# anna-b112-to-dip.net
KiCad netlist of a schematic drawn in EAGLE
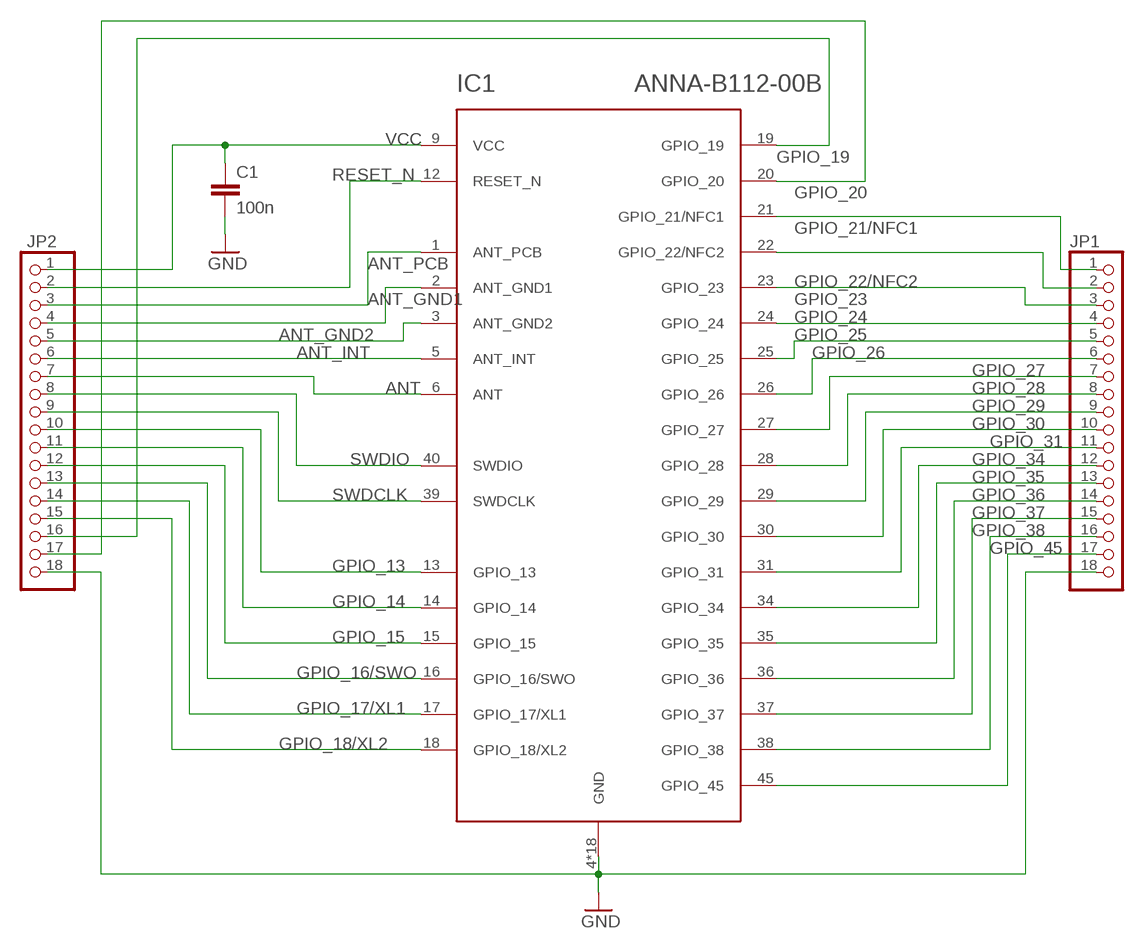
[diagram p0: schematic, sheet 1]

(export (version "E")
  (design (tool "Eeschema 10.0.6"))
  (components
    (comp (ref "C1")
      (value "100n")
      (footprint "eagle-import:C0805")
      (libsource (lib "eagle-import") (part "C-EUC0805"))
    )
    (comp (ref "IC1")
      (value "ANNA-B112-00B")
      (footprint "eagle-import:ANNA-B112")
      (libsource (lib "eagle-import") (part "ANNA-B112-00B"))
    )
    (comp (ref "JP1")
      (value "PINHD-1X18")
      (footprint "eagle-import:1X18")
      (libsource (lib "eagle-import") (part "PINHD-1X18"))
    )
    (comp (ref "JP2")
      (value "PINHD-1X18")
      (footprint "eagle-import:1X18")
      (libsource (lib "eagle-import") (part "PINHD-1X18"))
    )
  )
  (nets
    (net (code "1") (name "/ANT") (class "Default")
      (node (ref "IC1") (pin "6") (pinfunction "ANT_6") (pintype "bidirectional"))
      (node (ref "JP2") (pin "7") (pinfunction "7_7") (pintype "passive"))
    )
    (net (code "2") (name "/ANT_GND1") (class "Default")
      (node (ref "IC1") (pin "2") (pinfunction "ANT_GND1_2") (pintype "bidirectional"))
      (node (ref "JP2") (pin "4") (pinfunction "4_4") (pintype "passive"))
    )
    (net (code "3") (name "/ANT_GND2") (class "Default")
      (node (ref "IC1") (pin "3") (pinfunction "ANT_GND2_3") (pintype "bidirectional"))
      (node (ref "JP2") (pin "5") (pinfunction "5_5") (pintype "passive"))
    )
    (net (code "4") (name "/ANT_INT") (class "Default")
      (node (ref "IC1") (pin "5") (pinfunction "ANT_INT_5") (pintype "bidirectional"))
      (node (ref "JP2") (pin "6") (pinfunction "6_6") (pintype "passive"))
    )
    (net (code "5") (name "/ANT_PCB") (class "Default")
      (node (ref "IC1") (pin "1") (pinfunction "ANT_PCB_1") (pintype "bidirectional"))
      (node (ref "JP2") (pin "3") (pinfunction "3_3") (pintype "passive"))
    )
    (net (code "6") (name "/GPIO_13") (class "Default")
      (node (ref "IC1") (pin "13") (pinfunction "GPIO_13_13") (pintype "bidirectional"))
      (node (ref "JP2") (pin "10") (pinfunction "10_10") (pintype "passive"))
    )
    (net (code "7") (name "/GPIO_14") (class "Default")
      (node (ref "IC1") (pin "14") (pinfunction "GPIO_14_14") (pintype "bidirectional"))
      (node (ref "JP2") (pin "11") (pinfunction "11_11") (pintype "passive"))
    )
    (net (code "8") (name "/GPIO_15") (class "Default")
      (node (ref "IC1") (pin "15") (pinfunction "GPIO_15_15") (pintype "bidirectional"))
      (node (ref "JP2") (pin "12") (pinfunction "12_12") (pintype "passive"))
    )
    (net (code "9") (name "/GPIO_16{slash}SWO") (class "Default")
      (node (ref "IC1") (pin "16") (pinfunction "GPIO_16/SWO_16") (pintype "bidirectional"))
      (node (ref "JP2") (pin "13") (pinfunction "13_13") (pintype "passive"))
    )
    (net (code "10") (name "/GPIO_17{slash}XL1") (class "Default")
      (node (ref "IC1") (pin "17") (pinfunction "GPIO_17/XL1_17") (pintype "bidirectional"))
      (node (ref "JP2") (pin "14") (pinfunction "14_14") (pintype "passive"))
    )
    (net (code "11") (name "/GPIO_18{slash}XL2") (class "Default")
      (node (ref "IC1") (pin "18") (pinfunction "GPIO_18/XL2_18") (pintype "bidirectional"))
      (node (ref "JP2") (pin "15") (pinfunction "15_15") (pintype "passive"))
    )
    (net (code "12") (name "/GPIO_19") (class "Default")
      (node (ref "IC1") (pin "19") (pinfunction "GPIO_19_19") (pintype "bidirectional"))
      (node (ref "JP2") (pin "16") (pinfunction "16_16") (pintype "passive"))
    )
    (net (code "13") (name "/GPIO_20") (class "Default")
      (node (ref "IC1") (pin "20") (pinfunction "GPIO_20_20") (pintype "bidirectional"))
      (node (ref "JP2") (pin "17") (pinfunction "17_17") (pintype "passive"))
    )
    (net (code "14") (name "/GPIO_21{slash}NFC1") (class "Default")
      (node (ref "IC1") (pin "21") (pinfunction "GPIO_21/NFC1_21") (pintype "bidirectional"))
      (node (ref "JP1") (pin "1") (pinfunction "1_1") (pintype "passive"))
    )
    (net (code "15") (name "/GPIO_22{slash}NFC2") (class "Default")
      (node (ref "IC1") (pin "22") (pinfunction "GPIO_22/NFC2_22") (pintype "bidirectional"))
      (node (ref "JP1") (pin "2") (pinfunction "2_2") (pintype "passive"))
    )
    (net (code "16") (name "/GPIO_23") (class "Default")
      (node (ref "IC1") (pin "23") (pinfunction "GPIO_23_23") (pintype "bidirectional"))
      (node (ref "JP1") (pin "3") (pinfunction "3_3") (pintype "passive"))
    )
    (net (code "17") (name "/GPIO_24") (class "Default")
      (node (ref "IC1") (pin "24") (pinfunction "GPIO_24_24") (pintype "bidirectional"))
      (node (ref "JP1") (pin "4") (pinfunction "4_4") (pintype "passive"))
    )
    (net (code "18") (name "/GPIO_25") (class "Default")
      (node (ref "IC1") (pin "25") (pinfunction "GPIO_25_25") (pintype "bidirectional"))
      (node (ref "JP1") (pin "5") (pinfunction "5_5") (pintype "passive"))
    )
    (net (code "19") (name "/GPIO_26") (class "Default")
      (node (ref "IC1") (pin "26") (pinfunction "GPIO_26_26") (pintype "bidirectional"))
      (node (ref "JP1") (pin "6") (pinfunction "6_6") (pintype "passive"))
    )
    (net (code "20") (name "/GPIO_27") (class "Default")
      (node (ref "IC1") (pin "27") (pinfunction "GPIO_27_27") (pintype "bidirectional"))
      (node (ref "JP1") (pin "7") (pinfunction "7_7") (pintype "passive"))
    )
    (net (code "21") (name "/GPIO_28") (class "Default")
      (node (ref "IC1") (pin "28") (pinfunction "GPIO_28_28") (pintype "bidirectional"))
      (node (ref "JP1") (pin "8") (pinfunction "8_8") (pintype "passive"))
    )
    (net (code "22") (name "/GPIO_29") (class "Default")
      (node (ref "IC1") (pin "29") (pinfunction "GPIO_29_29") (pintype "bidirectional"))
      (node (ref "JP1") (pin "9") (pinfunction "9_9") (pintype "passive"))
    )
    (net (code "23") (name "/GPIO_30") (class "Default")
      (node (ref "IC1") (pin "30") (pinfunction "GPIO_30_30") (pintype "bidirectional"))
      (node (ref "JP1") (pin "10") (pinfunction "10_10") (pintype "passive"))
    )
    (net (code "24") (name "/GPIO_31") (class "Default")
      (node (ref "IC1") (pin "31") (pinfunction "GPIO_31_31") (pintype "bidirectional"))
      (node (ref "JP1") (pin "11") (pinfunction "11_11") (pintype "passive"))
    )
    (net (code "25") (name "/GPIO_34") (class "Default")
      (node (ref "IC1") (pin "34") (pinfunction "GPIO_34_34") (pintype "bidirectional"))
      (node (ref "JP1") (pin "12") (pinfunction "12_12") (pintype "passive"))
    )
    (net (code "26") (name "/GPIO_35") (class "Default")
      (node (ref "IC1") (pin "35") (pinfunction "GPIO_35_35") (pintype "bidirectional"))
      (node (ref "JP1") (pin "13") (pinfunction "13_13") (pintype "passive"))
    )
    (net (code "27") (name "/GPIO_36") (class "Default")
      (node (ref "IC1") (pin "36") (pinfunction "GPIO_36_36") (pintype "bidirectional"))
      (node (ref "JP1") (pin "14") (pinfunction "14_14") (pintype "passive"))
    )
    (net (code "28") (name "/GPIO_37") (class "Default")
      (node (ref "IC1") (pin "37") (pinfunction "GPIO_37_37") (pintype "bidirectional"))
      (node (ref "JP1") (pin "15") (pinfunction "15_15") (pintype "passive"))
    )
    (net (code "29") (name "/GPIO_38") (class "Default")
      (node (ref "IC1") (pin "38") (pinfunction "GPIO_38_38") (pintype "bidirectional"))
      (node (ref "JP1") (pin "16") (pinfunction "16_16") (pintype "passive"))
    )
    (net (code "30") (name "/GPIO_45") (class "Default")
      (node (ref "IC1") (pin "45") (pinfunction "GPIO_45_45") (pintype "bidirectional"))
      (node (ref "JP1") (pin "17") (pinfunction "17_17") (pintype "passive"))
    )
    (net (code "31") (name "/RESET_N") (class "Default")
      (node (ref "IC1") (pin "12") (pinfunction "RESET_N_12") (pintype "bidirectional"))
      (node (ref "JP2") (pin "2") (pinfunction "2_2") (pintype "passive"))
    )
    (net (code "32") (name "/SWDCLK") (class "Default")
      (node (ref "IC1") (pin "39") (pinfunction "SWDCLK_39") (pintype "bidirectional"))
      (node (ref "JP2") (pin "9") (pinfunction "9_9") (pintype "passive"))
    )
    (net (code "33") (name "/SWDIO") (class "Default")
      (node (ref "IC1") (pin "40") (pinfunction "SWDIO_40") (pintype "bidirectional"))
      (node (ref "JP2") (pin "8") (pinfunction "8_8") (pintype "passive"))
    )
    (net (code "34") (name "/VCC") (class "Default")
      (node (ref "C1") (pin "1") (pinfunction "1_1") (pintype "passive"))
      (node (ref "IC1") (pin "9") (pinfunction "VCC_9") (pintype "bidirectional"))
      (node (ref "JP2") (pin "1") (pinfunction "1_1") (pintype "passive"))
    )
    (net (code "35") (name "GND") (class "Default")
      (node (ref "C1") (pin "2") (pinfunction "2_2") (pintype "passive"))
      (node (ref "IC1") (pin "10") (pinfunction "GND_10") (pintype "bidirectional"))
      (node (ref "IC1") (pin "11") (pinfunction "GND_11") (pintype "bidirectional"))
      (node (ref "IC1") (pin "32") (pinfunction "GND_32") (pintype "bidirectional"))
      (node (ref "IC1") (pin "33") (pinfunction "GND_33") (pintype "bidirectional"))
      (node (ref "IC1") (pin "4") (pinfunction "GND_4") (pintype "bidirectional"))
      (node (ref "IC1") (pin "41") (pinfunction "GND_41") (pintype "bidirectional"))
      (node (ref "IC1") (pin "42") (pinfunction "GND_42") (pintype "bidirectional"))
      (node (ref "IC1") (pin "43") (pinfunction "GND_43") (pintype "bidirectional"))
      (node (ref "IC1") (pin "44") (pinfunction "GND_44") (pintype "bidirectional"))
      (node (ref "IC1") (pin "46") (pinfunction "GND_46") (pintype "bidirectional"))
      (node (ref "IC1") (pin "47") (pinfunction "GND_47") (pintype "bidirectional"))
      (node (ref "IC1") (pin "48") (pinfunction "GND_48") (pintype "bidirectional"))
      (node (ref "IC1") (pin "49") (pinfunction "GND_49") (pintype "bidirectional"))
      (node (ref "IC1") (pin "50") (pinfunction "GND_50") (pintype "bidirectional"))
      (node (ref "IC1") (pin "51") (pinfunction "GND_51") (pintype "bidirectional"))
      (node (ref "IC1") (pin "52") (pinfunction "GND_52") (pintype "bidirectional"))
      (node (ref "IC1") (pin "7") (pinfunction "GND_7") (pintype "bidirectional"))
      (node (ref "IC1") (pin "8") (pinfunction "GND_8") (pintype "bidirectional"))
      (node (ref "JP1") (pin "18") (pinfunction "18_18") (pintype "passive"))
      (node (ref "JP2") (pin "18") (pinfunction "18_18") (pintype "passive"))
    )
  )
)
